# GND_PLANE_32pinromtoflash_-_piggyback_28.net
KiCad netlist of a schematic drawn in EAGLE
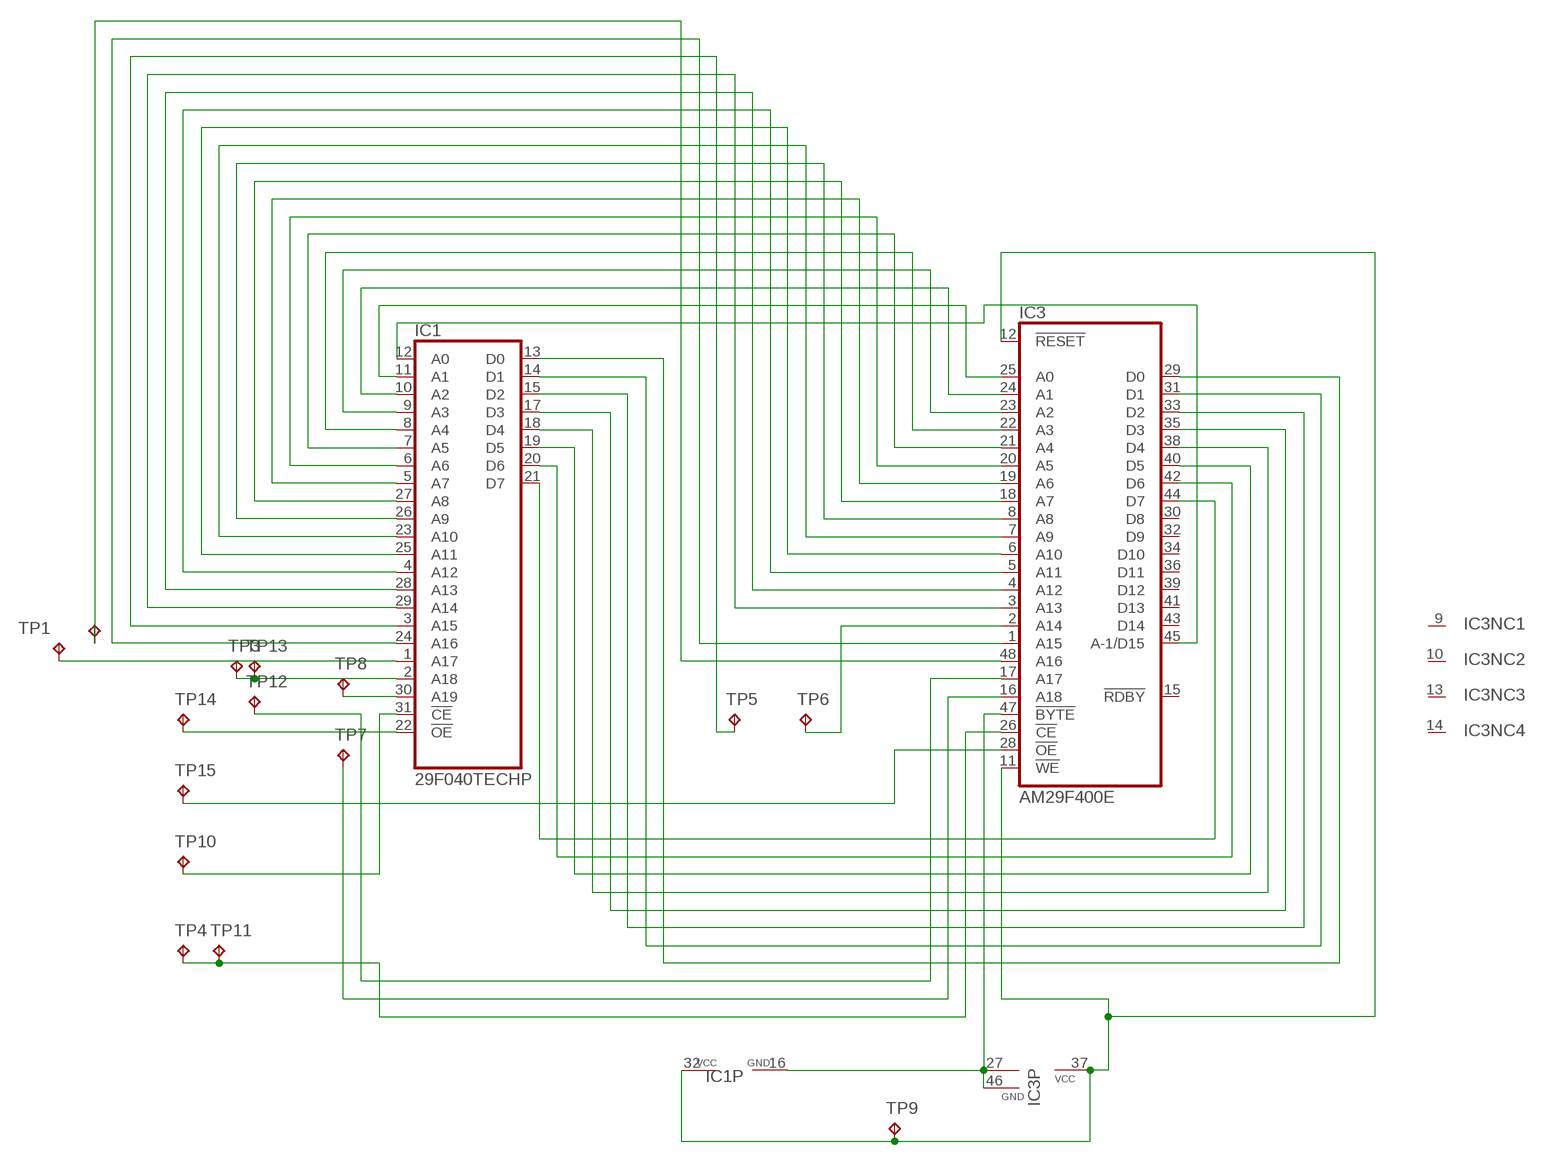
[diagram p0: schematic, sheet 1]

(export (version "E")
  (design (tool "Eeschema 10.0.6"))
  (components
    (comp (ref "IC1")
      (value "29F040TECHP")
      (footprint "eagle-import:DIL32-3")
      (libsource (lib "eagle-import") (part "29F040PTECH"))
    )
    (comp (ref "IC3")
      (value "AM29F400E")
      (footprint "eagle-import:TSOP48")
      (libsource (lib "eagle-import") (part "AM29F400E"))
    )
    (comp (ref "TP1")
      (value "TPTP15SQ")
      (footprint "eagle-import:TP15SQ")
      (libsource (lib "eagle-import") (part "TPTP15SQ"))
    )
    (comp (ref "TP2")
      (value "TPTP15SQ")
      (footprint "eagle-import:TP15SQ")
      (libsource (lib "eagle-import") (part "TPTP15SQ"))
    )
    (comp (ref "TP3")
      (value "TPTP15SQ")
      (footprint "eagle-import:TP15SQ")
      (libsource (lib "eagle-import") (part "TPTP15SQ"))
    )
    (comp (ref "TP4")
      (value "TPTP15SQ")
      (footprint "eagle-import:TP15SQ")
      (libsource (lib "eagle-import") (part "TPTP15SQ"))
    )
    (comp (ref "TP5")
      (value "TPTP15SQ")
      (footprint "eagle-import:TP15SQ")
      (libsource (lib "eagle-import") (part "TPTP15SQ"))
    )
    (comp (ref "TP6")
      (value "TPTP15SQ")
      (footprint "eagle-import:TP15SQ")
      (libsource (lib "eagle-import") (part "TPTP15SQ"))
    )
    (comp (ref "TP7")
      (value "TPTP15SQ")
      (footprint "eagle-import:TP15SQ")
      (libsource (lib "eagle-import") (part "TPTP15SQ"))
    )
    (comp (ref "TP8")
      (value "TPTP15SQ")
      (footprint "eagle-import:TP15SQ")
      (libsource (lib "eagle-import") (part "TPTP15SQ"))
    )
    (comp (ref "TP9")
      (value "TPTP15SQ")
      (footprint "eagle-import:TP15SQ")
      (libsource (lib "eagle-import") (part "TPTP15SQ"))
    )
    (comp (ref "TP10")
      (value "TPTP15SQ")
      (footprint "eagle-import:TP15SQ")
      (libsource (lib "eagle-import") (part "TPTP15SQ"))
    )
    (comp (ref "TP11")
      (value "TPTP15SQ")
      (footprint "eagle-import:TP15SQ")
      (libsource (lib "eagle-import") (part "TPTP15SQ"))
    )
    (comp (ref "TP12")
      (value "TPTP15SQ")
      (footprint "eagle-import:TP15SQ")
      (libsource (lib "eagle-import") (part "TPTP15SQ"))
    )
    (comp (ref "TP13")
      (value "TPTP15SQ")
      (footprint "eagle-import:TP15SQ")
      (libsource (lib "eagle-import") (part "TPTP15SQ"))
    )
    (comp (ref "TP14")
      (value "TPTP15SQ")
      (footprint "eagle-import:TP15SQ")
      (libsource (lib "eagle-import") (part "TPTP15SQ"))
    )
    (comp (ref "TP15")
      (value "TPTP15SQ")
      (footprint "eagle-import:TP15SQ")
      (libsource (lib "eagle-import") (part "TPTP15SQ"))
    )
  )
  (nets
    (net (code "1") (name "Net-(IC1A-A0)") (class "Default")
      (node (ref "IC1") (pin "12") (pinfunction "A0_12") (pintype "input"))
      (node (ref "IC3") (pin "45") (pinfunction "A-1/D15_45") (pintype "tri_state"))
    )
    (net (code "2") (name "Net-(IC1A-A1)") (class "Default")
      (node (ref "IC1") (pin "11") (pinfunction "A1_11") (pintype "input"))
      (node (ref "IC3") (pin "25") (pinfunction "A0_25") (pintype "input"))
    )
    (net (code "3") (name "Net-(IC1A-A2)") (class "Default")
      (node (ref "IC1") (pin "10") (pinfunction "A2_10") (pintype "input"))
      (node (ref "IC3") (pin "24") (pinfunction "A1_24") (pintype "input"))
    )
    (net (code "4") (name "Net-(IC1A-A3)") (class "Default")
      (node (ref "IC1") (pin "9") (pinfunction "A3_9") (pintype "input"))
      (node (ref "IC3") (pin "23") (pinfunction "A2_23") (pintype "input"))
    )
    (net (code "5") (name "Net-(IC1A-A4)") (class "Default")
      (node (ref "IC1") (pin "8") (pinfunction "A4_8") (pintype "input"))
      (node (ref "IC3") (pin "22") (pinfunction "A3_22") (pintype "input"))
    )
    (net (code "6") (name "Net-(IC1A-A5)") (class "Default")
      (node (ref "IC1") (pin "7") (pinfunction "A5_7") (pintype "input"))
      (node (ref "IC3") (pin "21") (pinfunction "A4_21") (pintype "input"))
    )
    (net (code "7") (name "Net-(IC1A-A6)") (class "Default")
      (node (ref "IC1") (pin "6") (pinfunction "A6_6") (pintype "input"))
      (node (ref "IC3") (pin "20") (pinfunction "A5_20") (pintype "input"))
    )
    (net (code "8") (name "Net-(IC1A-A7)") (class "Default")
      (node (ref "IC1") (pin "5") (pinfunction "A7_5") (pintype "input"))
      (node (ref "IC3") (pin "19") (pinfunction "A6_19") (pintype "input"))
    )
    (net (code "9") (name "Net-(IC1A-A8)") (class "Default")
      (node (ref "IC1") (pin "27") (pinfunction "A8_27") (pintype "input"))
      (node (ref "IC3") (pin "18") (pinfunction "A7_18") (pintype "input"))
    )
    (net (code "10") (name "Net-(IC1A-A9)") (class "Default")
      (node (ref "IC1") (pin "26") (pinfunction "A9_26") (pintype "input"))
      (node (ref "IC3") (pin "8") (pinfunction "A8_8") (pintype "input"))
    )
    (net (code "11") (name "Net-(IC1A-A10)") (class "Default")
      (node (ref "IC1") (pin "23") (pinfunction "A10_23") (pintype "input"))
      (node (ref "IC3") (pin "7") (pinfunction "A9_7") (pintype "input"))
    )
    (net (code "12") (name "Net-(IC1A-A11)") (class "Default")
      (node (ref "IC1") (pin "25") (pinfunction "A11_25") (pintype "input"))
      (node (ref "IC3") (pin "6") (pinfunction "A10_6") (pintype "input"))
    )
    (net (code "13") (name "Net-(IC1A-A12)") (class "Default")
      (node (ref "IC1") (pin "4") (pinfunction "A12_4") (pintype "input"))
      (node (ref "IC3") (pin "5") (pinfunction "A11_5") (pintype "input"))
    )
    (net (code "14") (name "Net-(IC1A-A13)") (class "Default")
      (node (ref "IC1") (pin "28") (pinfunction "A13_28") (pintype "input"))
      (node (ref "IC3") (pin "4") (pinfunction "A12_4") (pintype "input"))
    )
    (net (code "15") (name "Net-(IC1A-A14)") (class "Default")
      (node (ref "IC1") (pin "29") (pinfunction "A14_29") (pintype "input"))
      (node (ref "IC3") (pin "3") (pinfunction "A13_3") (pintype "input"))
    )
    (net (code "16") (name "Net-(IC1A-A15)") (class "Default")
      (node (ref "IC1") (pin "3") (pinfunction "A15_3") (pintype "input"))
      (node (ref "TP5") (pin "TP") (pinfunction "TP_TP") (pintype "input"))
    )
    (net (code "17") (name "Net-(IC1A-A16)") (class "Default")
      (node (ref "IC1") (pin "24") (pinfunction "A16_24") (pintype "input"))
      (node (ref "IC3") (pin "1") (pinfunction "A15_1") (pintype "input"))
    )
    (net (code "18") (name "Net-(IC1A-A17)") (class "Default")
      (node (ref "IC1") (pin "1") (pinfunction "A17_1") (pintype "input"))
      (node (ref "TP1") (pin "TP") (pinfunction "TP_TP") (pintype "input"))
    )
    (net (code "19") (name "Net-(IC1A-A18)") (class "Default")
      (node (ref "IC1") (pin "2") (pinfunction "A18_2") (pintype "input"))
      (node (ref "TP13") (pin "TP") (pinfunction "TP_TP") (pintype "input"))
      (node (ref "TP3") (pin "TP") (pinfunction "TP_TP") (pintype "input"))
    )
    (net (code "20") (name "Net-(IC1A-A19)") (class "Default")
      (node (ref "IC1") (pin "30") (pinfunction "A19_30") (pintype "input"))
      (node (ref "TP8") (pin "TP") (pinfunction "TP_TP") (pintype "input"))
    )
    (net (code "21") (name "Net-(IC1A-D0)") (class "Default")
      (node (ref "IC1") (pin "13") (pinfunction "D0_13") (pintype "tri_state"))
      (node (ref "IC3") (pin "29") (pinfunction "D0_29") (pintype "tri_state"))
    )
    (net (code "22") (name "Net-(IC1A-D1)") (class "Default")
      (node (ref "IC1") (pin "14") (pinfunction "D1_14") (pintype "tri_state"))
      (node (ref "IC3") (pin "31") (pinfunction "D1_31") (pintype "tri_state"))
    )
    (net (code "23") (name "Net-(IC1A-D2)") (class "Default")
      (node (ref "IC1") (pin "15") (pinfunction "D2_15") (pintype "tri_state"))
      (node (ref "IC3") (pin "33") (pinfunction "D2_33") (pintype "tri_state"))
    )
    (net (code "24") (name "Net-(IC1A-D3)") (class "Default")
      (node (ref "IC1") (pin "17") (pinfunction "D3_17") (pintype "tri_state"))
      (node (ref "IC3") (pin "35") (pinfunction "D3_35") (pintype "tri_state"))
    )
    (net (code "25") (name "Net-(IC1A-D4)") (class "Default")
      (node (ref "IC1") (pin "18") (pinfunction "D4_18") (pintype "tri_state"))
      (node (ref "IC3") (pin "38") (pinfunction "D4_38") (pintype "tri_state"))
    )
    (net (code "26") (name "Net-(IC1A-D5)") (class "Default")
      (node (ref "IC1") (pin "19") (pinfunction "D5_19") (pintype "tri_state"))
      (node (ref "IC3") (pin "40") (pinfunction "D5_40") (pintype "tri_state"))
    )
    (net (code "27") (name "Net-(IC1A-D6)") (class "Default")
      (node (ref "IC1") (pin "20") (pinfunction "D6_20") (pintype "tri_state"))
      (node (ref "IC3") (pin "42") (pinfunction "D6_42") (pintype "tri_state"))
    )
    (net (code "28") (name "Net-(IC1A-D7)") (class "Default")
      (node (ref "IC1") (pin "21") (pinfunction "D7_21") (pintype "input"))
      (node (ref "IC3") (pin "44") (pinfunction "D7_44") (pintype "tri_state"))
    )
    (net (code "29") (name "Net-(IC1A-~{CE})") (class "Default")
      (node (ref "IC1") (pin "31") (pinfunction "~{CE}_31") (pintype "input"))
      (node (ref "TP10") (pin "TP") (pinfunction "TP_TP") (pintype "input"))
    )
    (net (code "30") (name "Net-(IC1A-~{OE})") (class "Default")
      (node (ref "IC1") (pin "22") (pinfunction "~{OE}_22") (pintype "input"))
      (node (ref "TP14") (pin "TP") (pinfunction "TP_TP") (pintype "input"))
    )
    (net (code "31") (name "Net-(IC1B-GND)") (class "Default")
      (node (ref "IC1") (pin "16") (pinfunction "GND_16") (pintype "power_in"))
      (node (ref "IC3") (pin "27") (pinfunction "GND_27") (pintype "power_in"))
      (node (ref "IC3") (pin "46") (pinfunction "GND_46") (pintype "power_in"))
      (node (ref "IC3") (pin "47") (pinfunction "~{BYTE}_47") (pintype "input"))
    )
    (net (code "32") (name "Net-(IC1B-VCC)") (class "Default")
      (node (ref "IC1") (pin "32") (pinfunction "VCC_32") (pintype "power_in"))
      (node (ref "IC3") (pin "11") (pinfunction "~{WE}_11") (pintype "input"))
      (node (ref "IC3") (pin "12") (pinfunction "~{RESET}_12") (pintype "input"))
      (node (ref "IC3") (pin "37") (pinfunction "VCC_37") (pintype "power_in"))
      (node (ref "TP9") (pin "TP") (pinfunction "TP_TP") (pintype "input"))
    )
    (net (code "33") (name "Net-(IC3A-A14)") (class "Default")
      (node (ref "IC3") (pin "2") (pinfunction "A14_2") (pintype "input"))
      (node (ref "TP6") (pin "TP") (pinfunction "TP_TP") (pintype "input"))
    )
    (net (code "34") (name "Net-(IC3A-A16)") (class "Default")
      (node (ref "IC3") (pin "48") (pinfunction "A16_48") (pintype "input"))
      (node (ref "TP2") (pin "TP") (pinfunction "TP_TP") (pintype "input"))
    )
    (net (code "35") (name "Net-(IC3A-A17)") (class "Default")
      (node (ref "IC3") (pin "17") (pinfunction "A17_17") (pintype "input"))
      (node (ref "TP12") (pin "TP") (pinfunction "TP_TP") (pintype "input"))
    )
    (net (code "36") (name "Net-(IC3A-A18)") (class "Default")
      (node (ref "IC3") (pin "16") (pinfunction "A18_16") (pintype "input"))
      (node (ref "TP7") (pin "TP") (pinfunction "TP_TP") (pintype "input"))
    )
    (net (code "37") (name "Net-(IC3A-~{CE})") (class "Default")
      (node (ref "IC3") (pin "26") (pinfunction "~{CE}_26") (pintype "input"))
      (node (ref "TP11") (pin "TP") (pinfunction "TP_TP") (pintype "input"))
      (node (ref "TP4") (pin "TP") (pinfunction "TP_TP") (pintype "input"))
    )
    (net (code "38") (name "Net-(IC3A-~{OE})") (class "Default")
      (node (ref "IC3") (pin "28") (pinfunction "~{OE}_28") (pintype "input"))
      (node (ref "TP15") (pin "TP") (pinfunction "TP_TP") (pintype "input"))
    )
    (net (code "39") (name "unconnected-(IC3A-D8-Pad30)") (class "Default")
      (node (ref "IC3") (pin "30") (pinfunction "D8_30") (pintype "tri_state"))
    )
    (net (code "40") (name "unconnected-(IC3A-D9-Pad32)") (class "Default")
      (node (ref "IC3") (pin "32") (pinfunction "D9_32") (pintype "tri_state"))
    )
    (net (code "41") (name "unconnected-(IC3A-D10-Pad34)") (class "Default")
      (node (ref "IC3") (pin "34") (pinfunction "D10_34") (pintype "tri_state"))
    )
    (net (code "42") (name "unconnected-(IC3A-D11-Pad36)") (class "Default")
      (node (ref "IC3") (pin "36") (pinfunction "D11_36") (pintype "tri_state"))
    )
    (net (code "43") (name "unconnected-(IC3A-D12-Pad39)") (class "Default")
      (node (ref "IC3") (pin "39") (pinfunction "D12_39") (pintype "tri_state"))
    )
    (net (code "44") (name "unconnected-(IC3A-D13-Pad41)") (class "Default")
      (node (ref "IC3") (pin "41") (pinfunction "D13_41") (pintype "tri_state"))
    )
    (net (code "45") (name "unconnected-(IC3A-D14-Pad43)") (class "Default")
      (node (ref "IC3") (pin "43") (pinfunction "D14_43") (pintype "tri_state"))
    )
    (net (code "46") (name "unconnected-(IC3A-~{RDBY}-Pad15)") (class "Default")
      (node (ref "IC3") (pin "15") (pinfunction "~{RDBY}_15") (pintype "output"))
    )
    (net (code "47") (name "unconnected-(IC3B-NC-Pad9)") (class "Default")
      (node (ref "IC3") (pin "9") (pinfunction "NC_9") (pintype "no_connect"))
    )
    (net (code "48") (name "unconnected-(IC3C-NC-Pad10)") (class "Default")
      (node (ref "IC3") (pin "10") (pinfunction "NC_10") (pintype "no_connect"))
    )
    (net (code "49") (name "unconnected-(IC3D-NC-Pad13)") (class "Default")
      (node (ref "IC3") (pin "13") (pinfunction "NC_13") (pintype "no_connect"))
    )
    (net (code "50") (name "unconnected-(IC3E-NC-Pad14)") (class "Default")
      (node (ref "IC3") (pin "14") (pinfunction "NC_14") (pintype "no_connect"))
    )
  )
)
